# BEP33_2panel_v2b.net
KiCad netlist of a schematic drawn in EAGLE
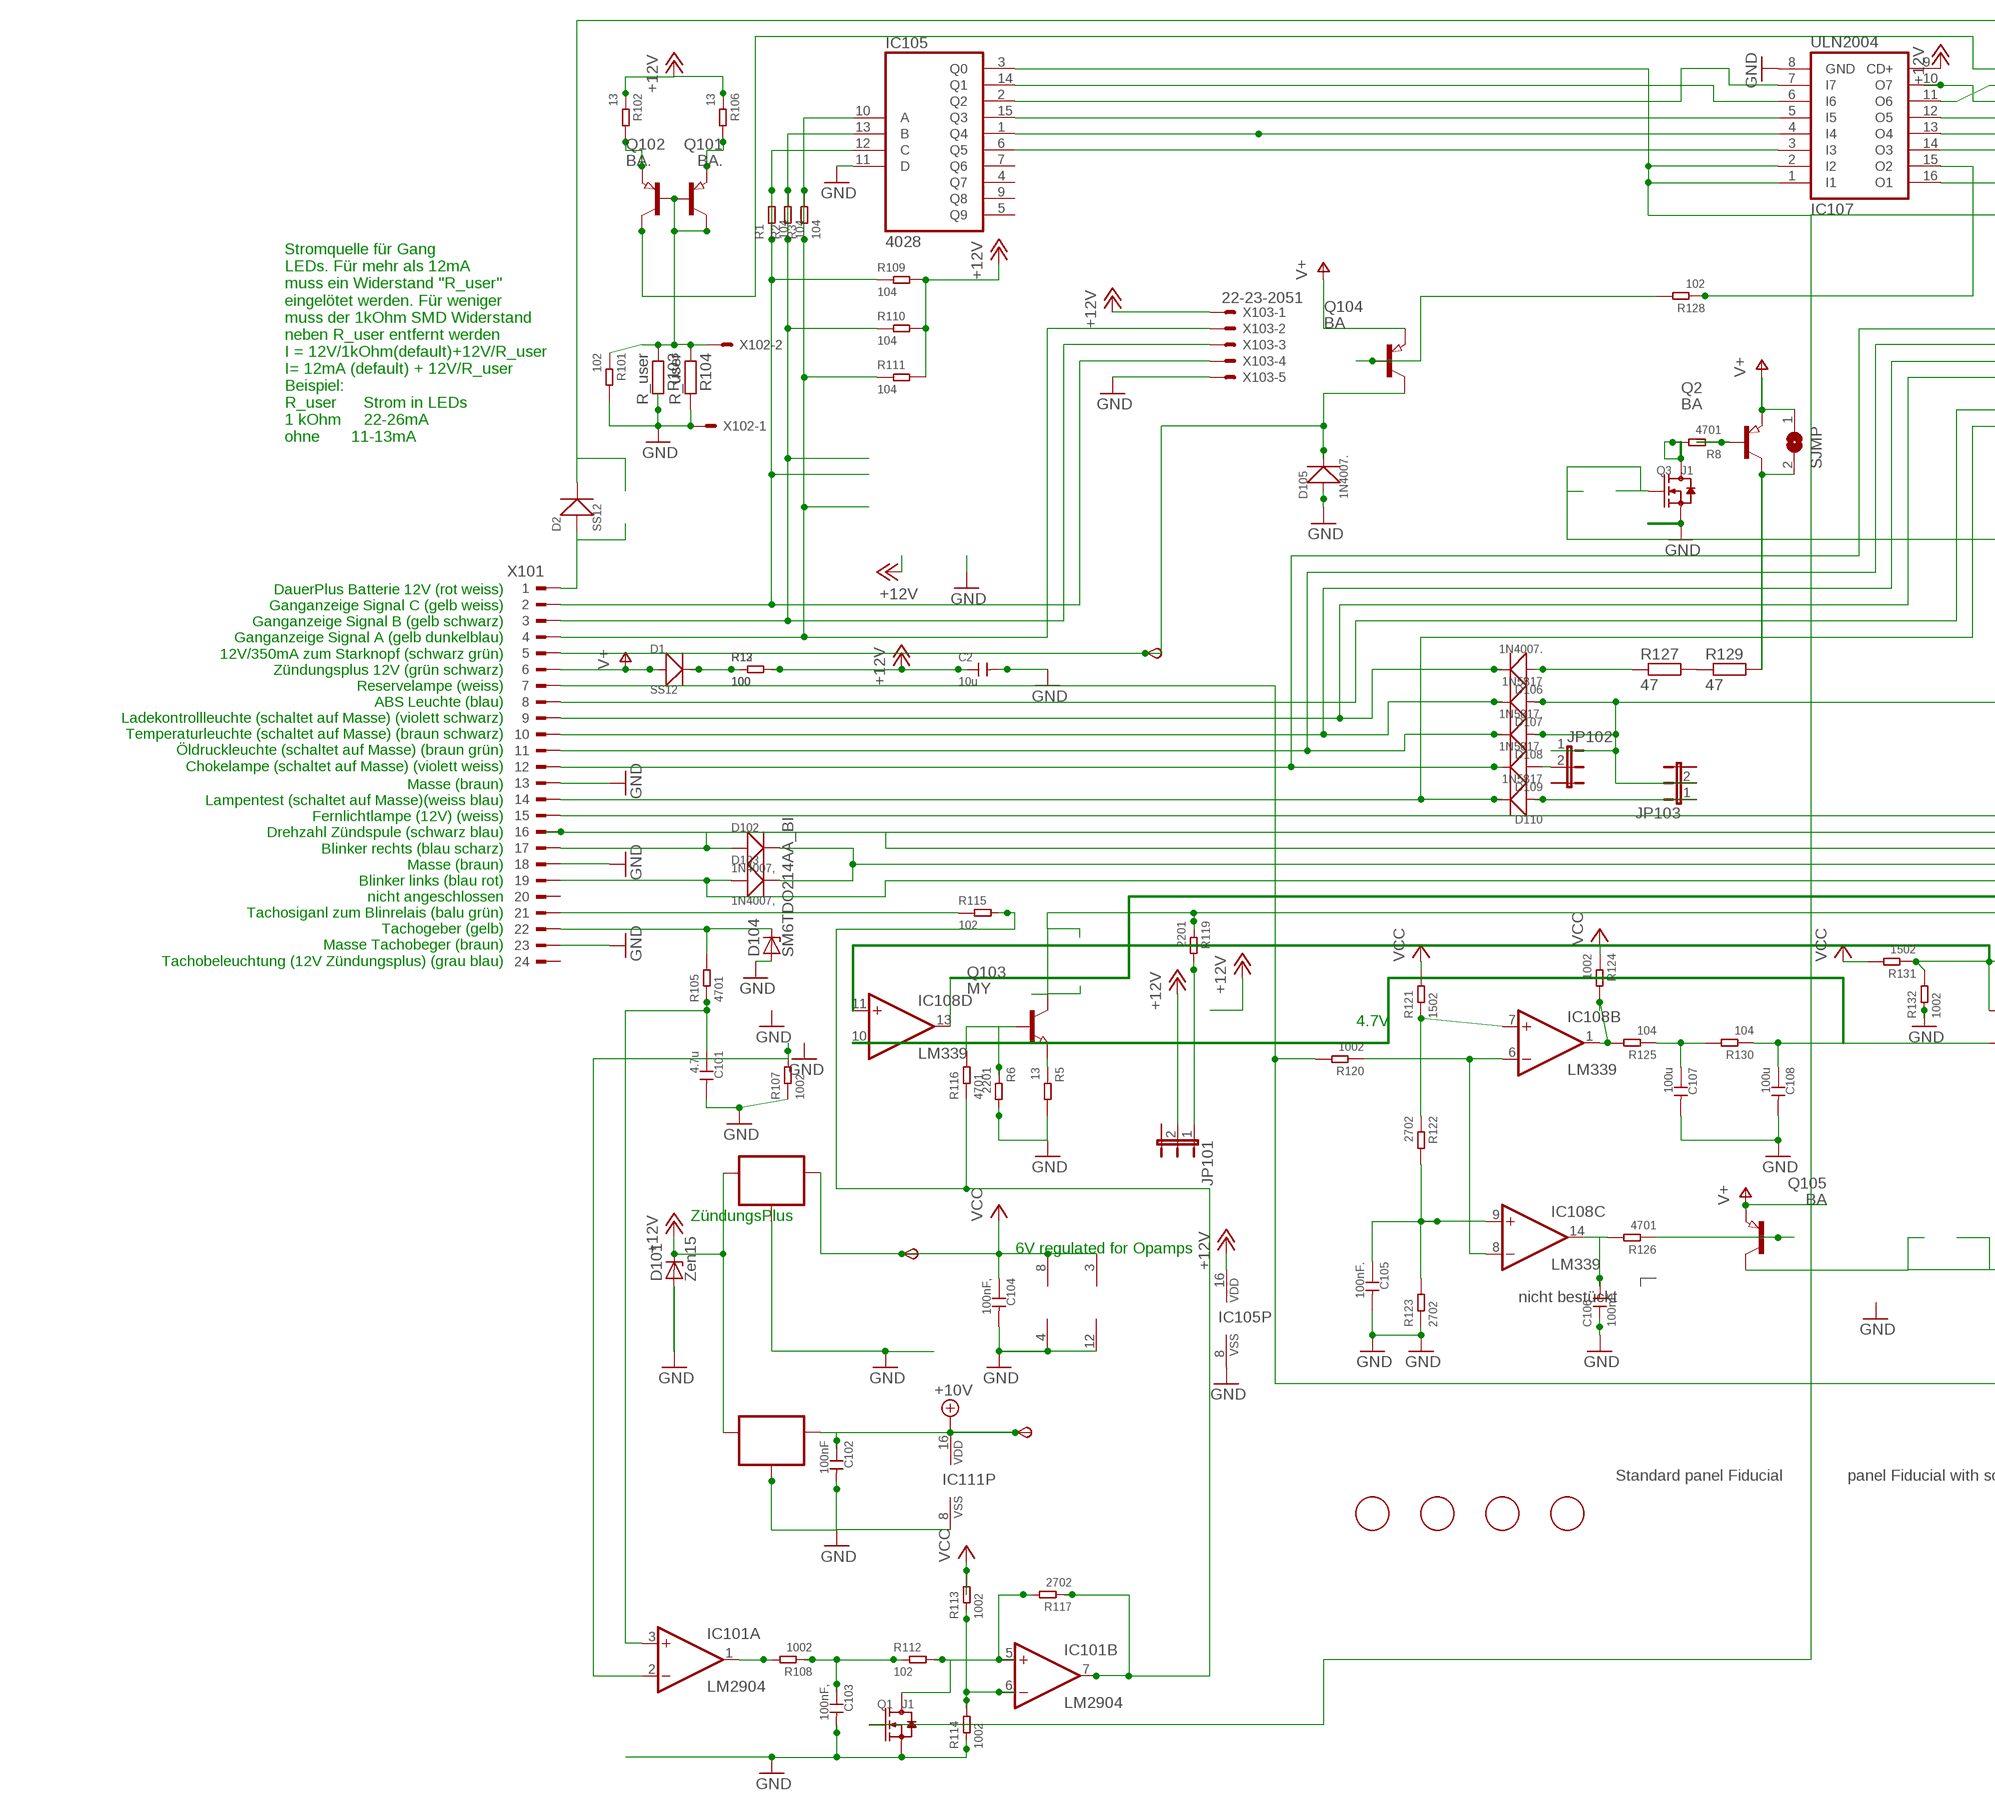
[diagram p0: schematic, sheet 1, part 1 of 2]
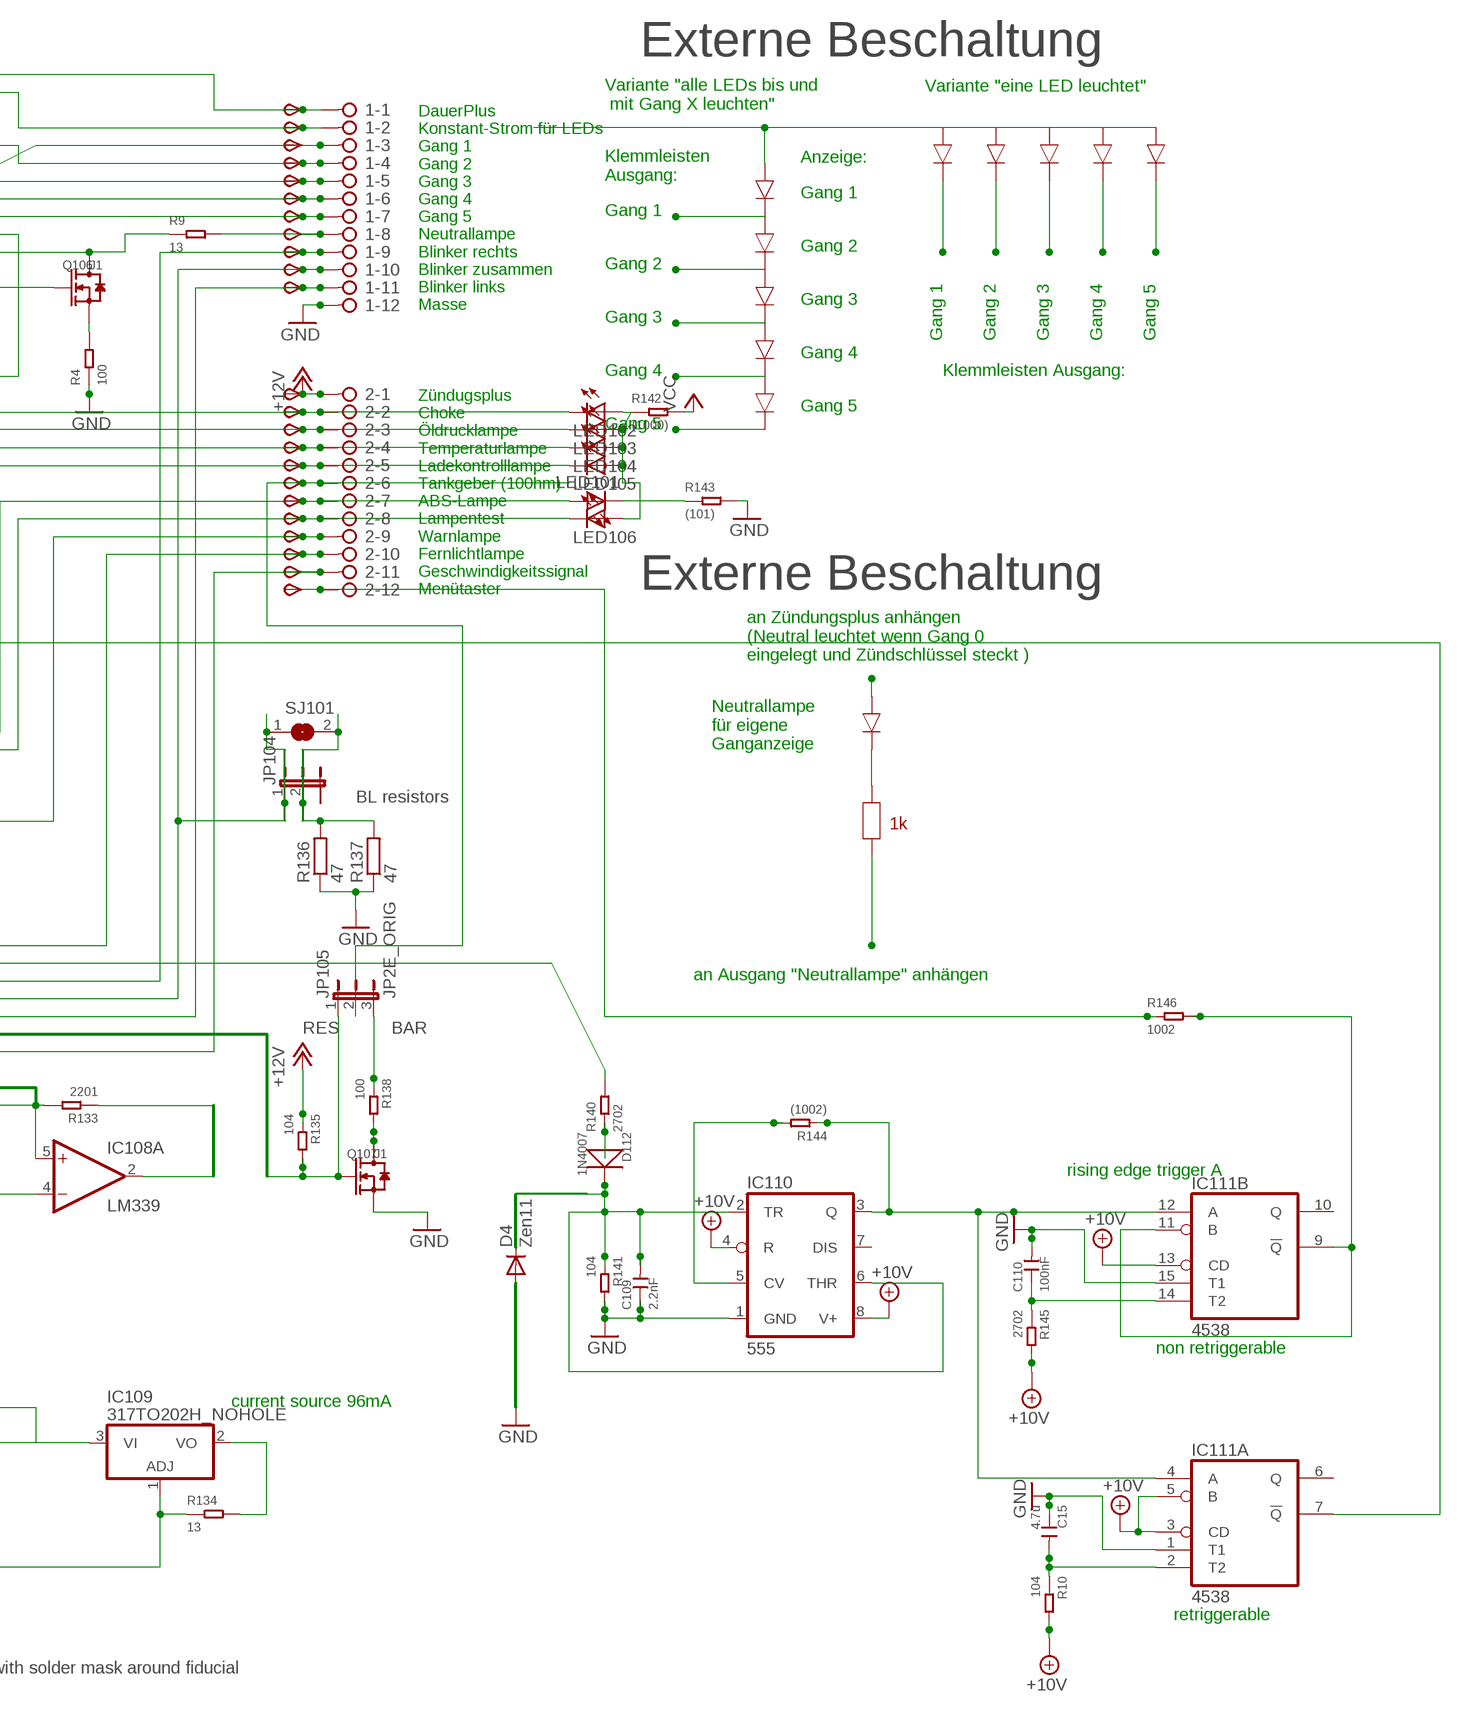
[diagram p1: schematic, sheet 1, part 2 of 2]

(export (version "E")
  (design (tool "Eeschema 10.0.6"))
  (components
    (comp (ref "1")
      (value "2081-1132")
      (footprint "eagle-import:12-PIN")
      (libsource (lib "eagle-import") (part "2081-1132"))
    )
    (comp (ref "2")
      (value "2081-1132")
      (footprint "eagle-import:12-PIN")
      (libsource (lib "eagle-import") (part "2081-1132"))
    )
    (comp (ref "6V")
      (value "TPSB2.0")
      (footprint "eagle-import:B2.0")
      (libsource (lib "eagle-import") (part "TPSB2.0"))
    )
    (comp (ref "10V")
      (value "TPSB2.0")
      (footprint "eagle-import:B2.0")
      (libsource (lib "eagle-import") (part "TPSB2.0"))
    )
    (comp (ref "C2")
      (value "10u")
      (footprint "eagle-import:C1206")
      (fields (field (name "MPN") "GRM31CR60J107ME39L"))
      (libsource (lib "eagle-import") (part "CERAMIC-100UF-6.3V-20%-X5R(1206)"))
    )
    (comp (ref "C15")
      (value "4.7u")
      (footprint "eagle-import:C0805")
      (fields (field (name "MPN") "CC0805KKX5R8BB475"))
      (libsource (lib "eagle-import") (part "CERAMIC-4.7UF-25V-10%-X5R(0805)"))
    )
    (comp (ref "C101")
      (value "4.7u")
      (footprint "eagle-import:C0805")
      (fields (field (name "MPN") "CC0805KKX5R8BB475"))
      (libsource (lib "eagle-import") (part "CERAMIC-4.7UF-25V-10%-X5R(0805)"))
    )
    (comp (ref "C102")
      (value "100nF")
      (footprint "eagle-import:C0805")
      (fields (field (name "MPN") "CC0805KRX7R9BB104"))
      (libsource (lib "eagle-import") (part "CERAMIC-100NF-50V-10%-X7R(0805)"))
    )
    (comp (ref "C103")
      (value "100nF,")
      (footprint "eagle-import:C0805")
      (fields (field (name "MPN") "CC0805KRX7R9BB104"))
      (libsource (lib "eagle-import") (part "CERAMIC-100NF-50V-10%-X7R(0805)"))
    )
    (comp (ref "C104")
      (value "100nF,")
      (footprint "eagle-import:C0805")
      (fields (field (name "MPN") "CC0805KRX7R9BB104"))
      (libsource (lib "eagle-import") (part "CERAMIC-100NF-50V-10%-X7R(0805)"))
    )
    (comp (ref "C105")
      (value "100nF.")
      (footprint "eagle-import:C0805")
      (fields (field (name "MPN") "CC0805KRX7R9BB104"))
      (libsource (lib "eagle-import") (part "CERAMIC-100NF-50V-10%-X7R(0805)"))
    )
    (comp (ref "C106")
      (value "100nF.")
      (footprint "eagle-import:C0805")
      (fields (field (name "MPN") "CC0805KRX7R9BB104"))
      (libsource (lib "eagle-import") (part "CERAMIC-100NF-50V-10%-X7R(0805)"))
    )
    (comp (ref "C107")
      (value "100u")
      (footprint "eagle-import:C1206")
      (fields (field (name "MPN") "GRM31CR60J107ME39L"))
      (libsource (lib "eagle-import") (part "CERAMIC-100UF-6.3V-20%-X5R(1206)"))
    )
    (comp (ref "C108")
      (value "100u")
      (footprint "eagle-import:C1206")
      (fields (field (name "MPN") "GRM31CR60J107ME39L"))
      (libsource (lib "eagle-import") (part "CERAMIC-100UF-6.3V-20%-X5R(1206)"))
    )
    (comp (ref "C109")
      (value "2.2nF")
      (footprint "eagle-import:C0805")
      (fields (field (name "MPN") "CC0805KRX7R9BB104"))
      (libsource (lib "eagle-import") (part "CERAMIC-100NF-50V-10%-X7R(0805)"))
    )
    (comp (ref "C110")
      (value "100nF")
      (footprint "eagle-import:C0805")
      (fields (field (name "MPN") "CC0805KRX7R9BB104"))
      (libsource (lib "eagle-import") (part "CERAMIC-100NF-50V-10%-X7R(0805)"))
    )
    (comp (ref "D1")
      (value "SS12")
      (footprint "eagle-import:DO-214AC_SLIM")
      (libsource (lib "eagle-import") (part "DIODE-GEN-PURPOSE-1KV-1A(DO-214AC)DO-214AC/1206"))
    )
    (comp (ref "D2")
      (value "SS12")
      (footprint "eagle-import:DO-214AC_SLIM")
      (libsource (lib "eagle-import") (part "DIODE-GEN-PURPOSE-1KV-1A(DO-214AC)DO-214AC/1206"))
    )
    (comp (ref "D4")
      (value "Zen11")
      (footprint "eagle-import:SOD-123_MINI-SMA")
      (libsource (lib "eagle-import") (part "CGRM400-G1"))
    )
    (comp (ref "D101")
      (value "Zen15")
      (footprint "eagle-import:DO214AA")
      (libsource (lib "eagle-import") (part "SM6T"))
    )
    (comp (ref "D102")
      (value "1N4007,")
      (footprint "eagle-import:DO-214AC")
      (fields (field (name "MPN") "1N4007"))
      (libsource (lib "eagle-import") (part "DIODE-GEN-PURPOSE-1KV-1A(DO-214AC)"))
    )
    (comp (ref "D103")
      (value "1N4007,")
      (footprint "eagle-import:DO-214AC")
      (fields (field (name "MPN") "1N4007"))
      (libsource (lib "eagle-import") (part "DIODE-GEN-PURPOSE-1KV-1A(DO-214AC)"))
    )
    (comp (ref "D104")
      (value "SM6TDO214AA_BI")
      (footprint "eagle-import:DO214AA_BI")
      (libsource (lib "eagle-import") (part "SM6TDO214AA_BI"))
    )
    (comp (ref "D105")
      (value "1N4007.")
      (footprint "eagle-import:DO-214AC")
      (fields (field (name "MPN") "1N4007"))
      (libsource (lib "eagle-import") (part "DIODE-GEN-PURPOSE-1KV-1A(DO-214AC)"))
    )
    (comp (ref "D106")
      (value "1N4007.")
      (footprint "eagle-import:DO-214AC")
      (fields (field (name "MPN") "1N4007"))
      (libsource (lib "eagle-import") (part "DIODE-GEN-PURPOSE-1KV-1A(DO-214AC)"))
    )
    (comp (ref "D107")
      (value "1N5817")
      (footprint "eagle-import:DO-214AC_SLIM")
      (libsource (lib "eagle-import") (part "DIODE-GEN-PURPOSE-1KV-1A(DO-214AC)DO-214AC/1206"))
    )
    (comp (ref "D108")
      (value "1N5817.")
      (footprint "eagle-import:DO-214AC_SLIM")
      (libsource (lib "eagle-import") (part "DIODE-GEN-PURPOSE-1KV-1A(DO-214AC)DO-214AC/1206"))
    )
    (comp (ref "D109")
      (value "1N5817.")
      (footprint "eagle-import:DO-214AC_SLIM")
      (libsource (lib "eagle-import") (part "DIODE-GEN-PURPOSE-1KV-1A(DO-214AC)DO-214AC/1206"))
    )
    (comp (ref "D110")
      (value "1N5817")
      (footprint "eagle-import:DO-214AC_SLIM")
      (libsource (lib "eagle-import") (part "DIODE-GEN-PURPOSE-1KV-1A(DO-214AC)DO-214AC/1206"))
    )
    (comp (ref "D112")
      (value "1N4007")
      (footprint "eagle-import:DO-214AC")
      (libsource (lib "eagle-import") (part "DIODE-GEN-PURPOSE-1KV-1A(DO-214AC)"))
    )
    (comp (ref "FID101")
      (value "FIDUCIAL")
      (footprint "eagle-import:FIDUCIAL_1MM")
      (libsource (lib "eagle-import") (part "FIDUCIAL"))
    )
    (comp (ref "FID102")
      (value "FIDUCIAL")
      (footprint "eagle-import:FIDUCIAL_1MM")
      (libsource (lib "eagle-import") (part "FIDUCIAL"))
    )
    (comp (ref "FID103")
      (value "FIDUCIAL")
      (footprint "eagle-import:FIDUCIAL_1MM")
      (libsource (lib "eagle-import") (part "FIDUCIAL"))
    )
    (comp (ref "FID104")
      (value "FIDUCIAL")
      (footprint "eagle-import:FIDUCIAL_1MM")
      (libsource (lib "eagle-import") (part "FIDUCIAL"))
    )
    (comp (ref "IC101")
      (value "LM2904")
      (footprint "eagle-import:SO08")
      (libsource (lib "eagle-import") (part "LM358D"))
    )
    (comp (ref "IC102")
      (value "78L06")
      (footprint "eagle-import:SOT89_ROUND")
      (libsource (lib "eagle-import") (part "78LXXSOT89_ROUND"))
    )
    (comp (ref "IC104")
      (value "78L10")
      (footprint "eagle-import:SOT89_ROUND")
      (libsource (lib "eagle-import") (part "78LXXSOT89_ROUND"))
    )
    (comp (ref "IC105")
      (value "4028")
      (footprint "eagle-import:SO16")
      (libsource (lib "eagle-import") (part "4028D"))
    )
    (comp (ref "IC107")
      (value "ULN2004")
      (footprint "eagle-import:SO16")
      (libsource (lib "eagle-import") (part "ULN2004AD"))
    )
    (comp (ref "IC108")
      (value "LM339")
      (footprint "eagle-import:SO14")
      (libsource (lib "eagle-import") (part "LM339D"))
    )
    (comp (ref "IC109")
      (value "317TO202H_NOHOLE")
      (footprint "eagle-import:TO220H_NOHOLE")
      (libsource (lib "eagle-import") (part "317TO202H_NOHOLE"))
    )
    (comp (ref "IC110")
      (value "555")
      (footprint "eagle-import:SO08")
      (libsource (lib "eagle-import") (part "555DNE"))
    )
    (comp (ref "IC111")
      (value "4538")
      (footprint "eagle-import:SO16")
      (libsource (lib "eagle-import") (part "4538D"))
    )
    (comp (ref "JP101")
      (value "JP2EJP2_SMALLPADS")
      (footprint "eagle-import:JP2_SMALLPADS")
      (libsource (lib "eagle-import") (part "JP2EJP2_SMALLPADS"))
    )
    (comp (ref "JP102")
      (value "JP2EJP2_SMALLPADS")
      (footprint "eagle-import:JP2_SMALLPADS")
      (libsource (lib "eagle-import") (part "JP2EJP2_SMALLPADS"))
    )
    (comp (ref "JP103")
      (value "JP2EJP2_SMALLPADS")
      (footprint "eagle-import:JP2_SMALLPADS")
      (libsource (lib "eagle-import") (part "JP2EJP2_SMALLPADS"))
    )
    (comp (ref "JP104")
      (value "JP2EJP2_SMALLPADS")
      (footprint "eagle-import:JP2_SMALLPADS")
      (libsource (lib "eagle-import") (part "JP2EJP2_SMALLPADS"))
    )
    (comp (ref "JP105")
      (value "JP2E_ORIG")
      (footprint "eagle-import:JP2_ORIG_SMALLPADS")
      (libsource (lib "eagle-import") (part "JP2E_ORIG"))
    )
    (comp (ref "LED101")
      (value "LEDLD260")
      (footprint "eagle-import:LD260")
      (libsource (lib "eagle-import") (part "LEDLD260"))
    )
    (comp (ref "LED102")
      (value "LEDLD260")
      (footprint "eagle-import:LD260")
      (libsource (lib "eagle-import") (part "LEDLD260"))
    )
    (comp (ref "LED103")
      (value "LEDLD260")
      (footprint "eagle-import:LD260")
      (libsource (lib "eagle-import") (part "LEDLD260"))
    )
    (comp (ref "LED104")
      (value "LEDLD260")
      (footprint "eagle-import:LD260")
      (libsource (lib "eagle-import") (part "LEDLD260"))
    )
    (comp (ref "LED105")
      (value "LEDLD260")
      (footprint "eagle-import:LD260")
      (libsource (lib "eagle-import") (part "LEDLD260"))
    )
    (comp (ref "LED106")
      (value "LEDLD260")
      (footprint "eagle-import:LD260")
      (libsource (lib "eagle-import") (part "LEDLD260"))
    )
    (comp (ref "Q1")
      (value "J1")
      (footprint "eagle-import:SOT-23")
      (fields (field (name "MPN") "BSS138W-7-F"))
      (libsource (lib "eagle-import") (part "SMD-MOSFET-N-CH-50V-200MA-BSS138W-7-F(SOT-23)"))
    )
    (comp (ref "Q2")
      (value "BA")
      (footprint "eagle-import:SOT89")
      (libsource (lib "eagle-import") (part "PNP-TRANSISTOR_SOT89"))
    )
    (comp (ref "Q3")
      (value "J1")
      (footprint "eagle-import:SOT-23")
      (fields (field (name "MPN") "BSS138W-7-F"))
      (libsource (lib "eagle-import") (part "SMD-MOSFET-N-CH-50V-200MA-BSS138W-7-F(SOT-23)"))
    )
    (comp (ref "Q101")
      (value "BA.")
      (footprint "eagle-import:SOT89")
      (libsource (lib "eagle-import") (part "PNP-TRANSISTOR_SOT89"))
    )
    (comp (ref "Q102")
      (value "BA.")
      (footprint "eagle-import:SOT89")
      (libsource (lib "eagle-import") (part "PNP-TRANSISTOR_SOT89"))
    )
    (comp (ref "Q103")
      (value "MY")
      (footprint "eagle-import:SOT89")
      (libsource (lib "eagle-import") (part "NPN-TRANSISTOR_SOT89"))
    )
    (comp (ref "Q104")
      (value "BA")
      (footprint "eagle-import:SOT89")
      (libsource (lib "eagle-import") (part "PNP-TRANSISTOR_SOT89"))
    )
    (comp (ref "Q105")
      (value "BA")
      (footprint "eagle-import:SOT89")
      (libsource (lib "eagle-import") (part "PNP-TRANSISTOR_SOT89"))
    )
    (comp (ref "Q106")
      (value "J1")
      (footprint "eagle-import:SOT-23")
      (fields (field (name "MPN") "BSS138W-7-F"))
      (libsource (lib "eagle-import") (part "SMD-MOSFET-N-CH-50V-200MA-BSS138W-7-F(SOT-23)"))
    )
    (comp (ref "Q107")
      (value "J1")
      (footprint "eagle-import:SOT-23")
      (fields (field (name "MPN") "BSS138W-7-F"))
      (libsource (lib "eagle-import") (part "SMD-MOSFET-N-CH-50V-200MA-BSS138W-7-F(SOT-23)"))
    )
    (comp (ref "R1")
      (value "104")
      (footprint "eagle-import:R0805")
      (fields (field (name "MPN") "RC0805FR-0710KL"))
      (libsource (lib "eagle-import") (part "SMD-RES-10K-1%-1/8W(0805)"))
    )
    (comp (ref "R2")
      (value "104")
      (footprint "eagle-import:R0805")
      (fields (field (name "MPN") "RC0805FR-0710KL"))
      (libsource (lib "eagle-import") (part "SMD-RES-10K-1%-1/8W(0805)"))
    )
    (comp (ref "R3")
      (value "104")
      (footprint "eagle-import:R0805")
      (fields (field (name "MPN") "RC0805FR-0710KL"))
      (libsource (lib "eagle-import") (part "SMD-RES-10K-1%-1/8W(0805)"))
    )
    (comp (ref "R4")
      (value "100")
      (footprint "eagle-import:R0805")
      (fields (field (name "MPN") "RC0805JR-07220RL"))
      (libsource (lib "eagle-import") (part "SMD-RES-220R-5%-1/8W(0805)"))
    )
    (comp (ref "R5")
      (value "13")
      (footprint "eagle-import:R1206")
      (fields (field (name "MPN") "RC1206JR-0713RL"))
      (libsource (lib "eagle-import") (part "SMD-RES-13R-5%-1/4W(1206)"))
    )
    (comp (ref "R6")
      (value "2201")
      (footprint "eagle-import:R0805")
      (fields (field (name "MPN") "RC0805JR-071KL"))
      (libsource (lib "eagle-import") (part "SMD-RES-1K-5%-1/8W(0805)"))
    )
    (comp (ref "R8")
      (value "4701")
      (footprint "eagle-import:R0805")
      (fields (field (name "MPN") "RC0805JR-074K7L"))
      (libsource (lib "eagle-import") (part "SMD-RES-4.7K-5%-1/8W(0805)"))
    )
    (comp (ref "R9")
      (value "13")
      (footprint "eagle-import:R1206")
      (fields (field (name "MPN") "RC1206JR-0713RL"))
      (libsource (lib "eagle-import") (part "SMD-RES-13R-5%-1/4W(1206)"))
    )
    (comp (ref "R10")
      (value "104")
      (footprint "eagle-import:R0805")
      (fields (field (name "MPN") "RC0805JR-074K7L"))
      (libsource (lib "eagle-import") (part "SMD-RES-4.7K-5%-1/8W(0805)"))
    )
    (comp (ref "R12")
      (value "100")
      (footprint "eagle-import:R0805")
      (fields (field (name "MPN") "RC0805JR-072K2L"))
      (libsource (lib "eagle-import") (part "SMD-RES-2.2K-5%-1/8W(0805)"))
    )
    (comp (ref "R13")
      (value "100")
      (footprint "eagle-import:R0805")
      (fields (field (name "MPN") "RC0805JR-072K2L"))
      (libsource (lib "eagle-import") (part "SMD-RES-2.2K-5%-1/8W(0805)"))
    )
    (comp (ref "R101")
      (value "102")
      (footprint "eagle-import:R0805")
      (fields (field (name "MPN") "RC0805JR-071KL"))
      (libsource (lib "eagle-import") (part "SMD-RES-1K-5%-1/8W(0805)"))
    )
    (comp (ref "R102")
      (value "13")
      (footprint "eagle-import:R1206")
      (fields (field (name "MPN") "RC1206JR-0713RL"))
      (libsource (lib "eagle-import") (part "SMD-RES-13R-5%-1/4W(1206)"))
    )
    (comp (ref "R103")
      (value "R_user")
      (footprint "eagle-import:R0805")
      (libsource (lib "eagle-import") (part "R-EU_R0805"))
    )
    (comp (ref "R104")
      (value "R_user")
      (footprint "eagle-import:R0805")
      (libsource (lib "eagle-import") (part "R-EU_R0805"))
    )
    (comp (ref "R105")
      (value "4701")
      (footprint "eagle-import:R0805")
      (fields (field (name "MPN") "RC0805JR-074K7L"))
      (libsource (lib "eagle-import") (part "SMD-RES-4.7K-5%-1/8W(0805)"))
    )
    (comp (ref "R106")
      (value "13")
      (footprint "eagle-import:R1206")
      (fields (field (name "MPN") "RC1206JR-0713RL"))
      (libsource (lib "eagle-import") (part "SMD-RES-13R-5%-1/4W(1206)"))
    )
    (comp (ref "R107")
      (value "1002")
      (footprint "eagle-import:R0805")
      (fields (field (name "MPN") "RC0805FR-0710KL"))
      (libsource (lib "eagle-import") (part "SMD-RES-10K-1%-1/8W(0805)"))
    )
    (comp (ref "R108")
      (value "1002")
      (footprint "eagle-import:R0805")
      (fields (field (name "MPN") "RC0805FR-0710KL"))
      (libsource (lib "eagle-import") (part "SMD-RES-10K-1%-1/8W(0805)"))
    )
    (comp (ref "R109")
      (value "104")
      (footprint "eagle-import:R0805")
      (fields (field (name "MPN") "RC0805FR-0710KL"))
      (libsource (lib "eagle-import") (part "SMD-RES-10K-1%-1/8W(0805)"))
    )
    (comp (ref "R110")
      (value "104")
      (footprint "eagle-import:R0805")
      (fields (field (name "MPN") "RC0805FR-0710KL"))
      (libsource (lib "eagle-import") (part "SMD-RES-10K-1%-1/8W(0805)"))
    )
    (comp (ref "R111")
      (value "104")
      (footprint "eagle-import:R0805")
      (fields (field (name "MPN") "RC0805FR-0710KL"))
      (libsource (lib "eagle-import") (part "SMD-RES-10K-1%-1/8W(0805)"))
    )
    (comp (ref "R112")
      (value "102")
      (footprint "eagle-import:R0805")
      (fields (field (name "MPN") "RC0805JR-071KL"))
      (libsource (lib "eagle-import") (part "SMD-RES-1K-5%-1/8W(0805)"))
    )
    (comp (ref "R113")
      (value "1002")
      (footprint "eagle-import:R0805")
      (fields (field (name "MPN") "RC0805JR-071KL"))
      (libsource (lib "eagle-import") (part "SMD-RES-1K-5%-1/8W(0805)"))
    )
    (comp (ref "R114")
      (value "1002")
      (footprint "eagle-import:R0805")
      (fields (field (name "MPN") "RC0805JR-071KL"))
      (libsource (lib "eagle-import") (part "SMD-RES-1K-5%-1/8W(0805)"))
    )
    (comp (ref "R115")
      (value "102")
      (footprint "eagle-import:R0805")
      (fields (field (name "MPN") "RC0805JR-07220RL"))
      (libsource (lib "eagle-import") (part "SMD-RES-220R-5%-1/8W(0805)"))
    )
    (comp (ref "R116")
      (value "4701")
      (footprint "eagle-import:R0805")
      (fields (field (name "MPN") "RC0805JR-074K7L"))
      (libsource (lib "eagle-import") (part "SMD-RES-4.7K-5%-1/8W(0805)"))
    )
    (comp (ref "R117")
      (value "2702")
      (footprint "eagle-import:R0805")
      (fields (field (name "MPN") "RC0805JR-074K7L"))
      (libsource (lib "eagle-import") (part "SMD-RES-4.7K-5%-1/8W(0805)"))
    )
    (comp (ref "R119")
      (value "2201")
      (footprint "eagle-import:R0805")
      (fields (field (name "MPN") "RC0805JR-072K2L"))
      (libsource (lib "eagle-import") (part "SMD-RES-2.2K-5%-1/8W(0805)"))
    )
    (comp (ref "R120")
      (value "1002")
      (footprint "eagle-import:R0805")
      (fields (field (name "MPN") "RC0805FR-0710KL"))
      (libsource (lib "eagle-import") (part "SMD-RES-10K-1%-1/8W(0805)"))
    )
    (comp (ref "R121")
      (value "1502")
      (footprint "eagle-import:R0805")
      (fields (field (name "MPN") "RC0805FR-0710KL"))
      (libsource (lib "eagle-import") (part "SMD-RES-10K-1%-1/8W(0805)"))
    )
    (comp (ref "R122")
      (value "2702")
      (footprint "eagle-import:R0805")
      (fields (field (name "MPN") "RC0805JR-074K7L"))
      (libsource (lib "eagle-import") (part "SMD-RES-4.7K-5%-1/8W(0805)"))
    )
    (comp (ref "R123")
      (value "2702")
      (footprint "eagle-import:R0805")
      (fields (field (name "MPN") "RC0805JR-074K7L"))
      (libsource (lib "eagle-import") (part "SMD-RES-4.7K-5%-1/8W(0805)"))
    )
    (comp (ref "R124")
      (value "1002")
      (footprint "eagle-import:R0805")
      (fields (field (name "MPN") "RC0805FR-0710KL"))
      (libsource (lib "eagle-import") (part "SMD-RES-10K-1%-1/8W(0805)"))
    )
    (comp (ref "R125")
      (value "104")
      (footprint "eagle-import:R0805")
      (fields (field (name "MPN") "RC0805FR-0710KL"))
      (libsource (lib "eagle-import") (part "SMD-RES-10K-1%-1/8W(0805)"))
    )
    (comp (ref "R126")
      (value "4701")
      (footprint "eagle-import:R0805")
      (fields (field (name "MPN") "RC0805JR-074K7L"))
      (libsource (lib "eagle-import") (part "SMD-RES-4.7K-5%-1/8W(0805)"))
    )
    (comp (ref "R127")
      (value "47")
      (footprint "eagle-import:V235_17_1MM")
      (libsource (lib "eagle-import") (part "R-EU_V235/17_1MM"))
    )
    (comp (ref "R128")
      (value "102")
      (footprint "eagle-import:R0805")
      (fields (field (name "MPN") "RC0805JR-071KL"))
      (libsource (lib "eagle-import") (part "SMD-RES-1K-5%-1/8W(0805)"))
    )
    (comp (ref "R129")
      (value "47")
      (footprint "eagle-import:V235_17_1MM")
      (libsource (lib "eagle-import") (part "R-EU_V235/17_1MM"))
    )
    (comp (ref "R130")
      (value "104")
      (footprint "eagle-import:R0805")
      (fields (field (name "MPN") "RC0805FR-0710KL"))
      (libsource (lib "eagle-import") (part "SMD-RES-10K-1%-1/8W(0805)"))
    )
    (comp (ref "R131")
      (value "1502")
      (footprint "eagle-import:R0805")
      (fields (field (name "MPN") "RC0805FR-0710KL"))
      (libsource (lib "eagle-import") (part "SMD-RES-10K-1%-1/8W(0805)"))
    )
    (comp (ref "R132")
      (value "1002")
      (footprint "eagle-import:R0805")
      (fields (field (name "MPN") "RC0805FR-0710KL"))
      (libsource (lib "eagle-import") (part "SMD-RES-10K-1%-1/8W(0805)"))
    )
    (comp (ref "R133")
      (value "2201")
      (footprint "eagle-import:R0805")
      (fields (field (name "MPN") "RC0805JR-072K2L"))
      (libsource (lib "eagle-import") (part "SMD-RES-2.2K-5%-1/8W(0805)"))
    )
    (comp (ref "R134")
      (value "13")
      (footprint "eagle-import:R1206")
      (fields (field (name "MPN") "RC1206JR-0713RL"))
      (libsource (lib "eagle-import") (part "SMD-RES-13R-5%-1/4W(1206)"))
    )
    (comp (ref "R135")
      (value "104")
      (footprint "eagle-import:R0805")
      (fields (field (name "MPN") "RC0805FR-0710KL"))
      (libsource (lib "eagle-import") (part "SMD-RES-10K-1%-1/8W(0805)"))
    )
    (comp (ref "R136")
      (value "47")
      (footprint "eagle-import:V235_17_1MM")
      (libsource (lib "eagle-import") (part "R-EU_V235/17_1MM"))
    )
    (comp (ref "R137")
      (value "47")
      (footprint "eagle-import:V235_17_1MM")
      (libsource (lib "eagle-import") (part "R-EU_V235/17_1MM"))
    )
    (comp (ref "R138")
      (value "100")
      (footprint "eagle-import:R0805")
      (fields (field (name "MPN") "RC0805JR-072K2L"))
      (libsource (lib "eagle-import") (part "SMD-RES-2.2K-5%-1/8W(0805)"))
    )
    (comp (ref "R140")
      (value "2702")
      (footprint "eagle-import:R0805")
      (fields (field (name "MPN") "RC0805FR-0710KL"))
      (libsource (lib "eagle-import") (part "SMD-RES-10K-1%-1/8W(0805)"))
    )
    (comp (ref "R141")
      (value "104")
      (footprint "eagle-import:R0805")
      (fields (field (name "MPN") "RC0805FR-0710KL"))
      (libsource (lib "eagle-import") (part "SMD-RES-10K-1%-1/8W(0805)"))
    )
    (comp (ref "R142")
      (value "(1000)")
      (footprint "eagle-import:R0805")
      (fields (field (name "MPN") "RC0805JR-07100RL"))
      (libsource (lib "eagle-import") (part "SMD-RES-100R-5%-1/8W(0805)"))
    )
    (comp (ref "R143")
      (value "(101)")
      (footprint "eagle-import:R0805")
      (fields (field (name "MPN") "RC0805JR-07100RL"))
      (libsource (lib "eagle-import") (part "SMD-RES-100R-5%-1/8W(0805)"))
    )
    (comp (ref "R144")
      (value "(1002)")
      (footprint "eagle-import:R0805")
      (fields (field (name "MPN") "RC0805FR-0710KL"))
      (libsource (lib "eagle-import") (part "SMD-RES-10K-1%-1/8W(0805)"))
    )
    (comp (ref "R145")
      (value "2702")
      (footprint "eagle-import:R0805")
      (fields (field (name "MPN") "RC0805JR-074K7L"))
      (libsource (lib "eagle-import") (part "SMD-RES-4.7K-5%-1/8W(0805)"))
    )
    (comp (ref "R146")
      (value "1002")
      (footprint "eagle-import:R0805")
      (fields (field (name "MPN") "RC0805JR-074K7L"))
      (libsource (lib "eagle-import") (part "SMD-RES-4.7K-5%-1/8W(0805)"))
    )
    (comp (ref "SJ101")
      (value "SJ")
      (footprint "eagle-import:SJ")
      (libsource (lib "eagle-import") (part "solder-jumper_SJ"))
    )
    (comp (ref "SJMP")
      (value "SJ")
      (footprint "eagle-import:SJ")
      (libsource (lib "eagle-import") (part "SJ"))
    )
    (comp (ref "START")
      (value "TPSB2.0")
      (footprint "eagle-import:B2.0")
      (libsource (lib "eagle-import") (part "TPSB2.0"))
    )
    (comp (ref "TP1")
      (value "TPSB2.0")
      (footprint "eagle-import:B2.0")
      (libsource (lib "eagle-import") (part "TPSB2.0"))
    )
    (comp (ref "TP2")
      (value "TPSB2.0")
      (footprint "eagle-import:B2.0")
      (libsource (lib "eagle-import") (part "TPSB2.0"))
    )
    (comp (ref "TP3")
      (value "TPSB2.0")
      (footprint "eagle-import:B2.0")
      (libsource (lib "eagle-import") (part "TPSB2.0"))
    )
    (comp (ref "TP4")
      (value "TPSB2.0")
      (footprint "eagle-import:B2.0")
      (libsource (lib "eagle-import") (part "TPSB2.0"))
    )
    (comp (ref "TP5")
      (value "TPSB2.0")
      (footprint "eagle-import:B2.0")
      (libsource (lib "eagle-import") (part "TPSB2.0"))
    )
    (comp (ref "TP6")
      (value "TPSB2.0")
      (footprint "eagle-import:B2.0")
      (libsource (lib "eagle-import") (part "TPSB2.0"))
    )
    (comp (ref "TP7")
      (value "TPSB2.0")
      (footprint "eagle-import:B2.0")
      (libsource (lib "eagle-import") (part "TPSB2.0"))
    )
    (comp (ref "TP8")
      (value "TPSB2.0")
      (footprint "eagle-import:B2.0")
      (libsource (lib "eagle-import") (part "TPSB2.0"))
    )
    (comp (ref "TP9")
      (value "TPSB2.0")
      (footprint "eagle-import:B2.0")
      (libsource (lib "eagle-import") (part "TPSB2.0"))
    )
    (comp (ref "TP10")
      (value "TPSB2.0")
      (footprint "eagle-import:B2.0")
      (libsource (lib "eagle-import") (part "TPSB2.0"))
    )
    (comp (ref "TP11")
      (value "TPSB2.0")
      (footprint "eagle-import:B2.0")
      (libsource (lib "eagle-import") (part "TPSB2.0"))
    )
    (comp (ref "TP12")
      (value "TPSB2.0")
      (footprint "eagle-import:B2.0")
      (libsource (lib "eagle-import") (part "TPSB2.0"))
    )
    (comp (ref "TP13")
      (value "TPSB2.0")
      (footprint "eagle-import:B2.0")
      (libsource (lib "eagle-import") (part "TPSB2.0"))
    )
    (comp (ref "TP16")
      (value "TPSB2.0")
      (footprint "eagle-import:B2.0")
      (libsource (lib "eagle-import") (part "TPSB2.0"))
    )
    (comp (ref "TP17")
      (value "TPSB2.0")
      (footprint "eagle-import:B2.0")
      (libsource (lib "eagle-import") (part "TPSB2.0"))
    )
    (comp (ref "TP18")
      (value "TPSB2.0")
      (footprint "eagle-import:B2.0")
      (libsource (lib "eagle-import") (part "TPSB2.0"))
    )
    (comp (ref "TP19")
      (value "TPSB2.0")
      (footprint "eagle-import:B2.0")
      (libsource (lib "eagle-import") (part "TPSB2.0"))
    )
    (comp (ref "TP21")
      (value "TPSB2.0")
      (footprint "eagle-import:B2.0")
      (libsource (lib "eagle-import") (part "TPSB2.0"))
    )
    (comp (ref "TP22")
      (value "TPSB2.0")
      (footprint "eagle-import:B2.0")
      (libsource (lib "eagle-import") (part "TPSB2.0"))
    )
    (comp (ref "TP23")
      (value "TPSB2.0")
      (footprint "eagle-import:B2.0")
      (libsource (lib "eagle-import") (part "TPSB2.0"))
    )
    (comp (ref "TP24")
      (value "TPSB1,27")
      (footprint "eagle-import:B1,27")
      (libsource (lib "eagle-import") (part "TPSB1,27"))
    )
    (comp (ref "TP25")
      (value "TPSB2.0")
      (footprint "eagle-import:B2.0")
      (libsource (lib "eagle-import") (part "TPSB2.0"))
    )
    (comp (ref "TP26")
      (value "TPSB2.0")
      (footprint "eagle-import:B2.0")
      (libsource (lib "eagle-import") (part "TPSB2.0"))
    )
    (comp (ref "X101")
      (value "CON_BMWV2")
      (footprint "eagle-import:24-PIN_V2")
      (libsource (lib "eagle-import") (part "CON_BMWV2"))
    )
    (comp (ref "X102")
      (value "22-23-2021")
      (footprint "eagle-import:22-23-2021")
      (fields (field (name "MF") "MOLEX"))
      (libsource (lib "eagle-import") (part "22-23-2021"))
    )
    (comp (ref "X103")
      (value "22-23-2051")
      (footprint "eagle-import:22-23-2051")
      (fields (field (name "MF") "MOLEX"))
      (libsource (lib "eagle-import") (part "22-23-2051"))
    )
  )
  (nets
    (net (code "1") (name "+10V") (class "Default")
      (node (ref "10V") (pin "TP") (pinfunction "PP_TP") (pintype "input"))
      (node (ref "C102") (pin "1") (pinfunction "1_1") (pintype "passive"))
      (node (ref "IC104") (pin "1") (pinfunction "OUT_1") (pintype "passive"))
      (node (ref "IC110") (pin "4") (pinfunction "R_4") (pintype "input"))
      (node (ref "IC110") (pin "8") (pinfunction "V+_8") (pintype "power_in"))
      (node (ref "IC111") (pin "13") (pinfunction "CD_13") (pintype "input"))
      (node (ref "IC111") (pin "16") (pinfunction "VDD_16") (pintype "power_in"))
      (node (ref "IC111") (pin "3") (pinfunction "CD_3") (pintype "input"))
      (node (ref "IC111") (pin "5") (pinfunction "B_5") (pintype "input"))
      (node (ref "R10") (pin "2") (pinfunction "2_2") (pintype "passive"))
      (node (ref "R145") (pin "2") (pinfunction "2_2") (pintype "passive"))
    )
    (net (code "2") (name "+12V") (class "Default")
      (node (ref "2") (pin "1") (pinfunction "KL_1") (pintype "passive"))
      (node (ref "C2") (pin "1") (pinfunction "1_1") (pintype "passive"))
      (node (ref "D101") (pin "C") (pinfunction "C_C") (pintype "passive"))
      (node (ref "IC102") (pin "3") (pinfunction "IN_3") (pintype "input"))
      (node (ref "IC104") (pin "3") (pinfunction "IN_3") (pintype "input"))
      (node (ref "IC105") (pin "16") (pinfunction "VDD_16") (pintype "power_in"))
      (node (ref "IC107") (pin "9") (pinfunction "CD+_9") (pintype "passive"))
      (node (ref "JP101") (pin "2") (pinfunction "2_2") (pintype "passive"))
      (node (ref "R102") (pin "1") (pinfunction "1_1") (pintype "passive"))
      (node (ref "R106") (pin "1") (pinfunction "1_1") (pintype "passive"))
      (node (ref "R109") (pin "2") (pinfunction "2_2") (pintype "passive"))
      (node (ref "R110") (pin "2") (pinfunction "2_2") (pintype "passive"))
      (node (ref "R111") (pin "2") (pinfunction "2_2") (pintype "passive"))
      (node (ref "R12") (pin "2") (pinfunction "2_2") (pintype "passive"))
      (node (ref "R13") (pin "2") (pinfunction "2_2") (pintype "passive"))
      (node (ref "R135") (pin "1") (pinfunction "1_1") (pintype "passive"))
      (node (ref "TP12") (pin "TP") (pinfunction "PP_TP") (pintype "input"))
      (node (ref "X103") (pin "1") (pinfunction "S_1") (pintype "passive"))
    )
    (net (code "3") (name "GND") (class "Default")
      (node (ref "1") (pin "12") (pinfunction "KL_12") (pintype "passive"))
      (node (ref "C101") (pin "2") (pinfunction "2_2") (pintype "passive"))
      (node (ref "C102") (pin "2") (pinfunction "2_2") (pintype "passive"))
      (node (ref "C103") (pin "2") (pinfunction "2_2") (pintype "passive"))
      (node (ref "C104") (pin "2") (pinfunction "2_2") (pintype "passive"))
      (node (ref "C105") (pin "2") (pinfunction "2_2") (pintype "passive"))
      (node (ref "C106") (pin "1") (pinfunction "1_1") (pintype "passive"))
      (node (ref "C107") (pin "2") (pinfunction "2_2") (pintype "passive"))
      (node (ref "C108") (pin "2") (pinfunction "2_2") (pintype "passive"))
      (node (ref "C109") (pin "1") (pinfunction "1_1") (pintype "passive"))
      (node (ref "C110") (pin "2") (pinfunction "2_2") (pintype "passive"))
      (node (ref "C15") (pin "1") (pinfunction "1_1") (pintype "passive"))
      (node (ref "C2") (pin "2") (pinfunction "2_2") (pintype "passive"))
      (node (ref "D101") (pin "A") (pinfunction "A_A") (pintype "passive"))
      (node (ref "D104") (pin "A") (pinfunction "A_A") (pintype "passive"))
      (node (ref "D105") (pin "1") (pinfunction "+_1") (pintype "passive"))
      (node (ref "D4") (pin "A") (pinfunction "A_A") (pintype "passive"))
      (node (ref "IC101") (pin "4") (pinfunction "V-_4") (pintype "power_in"))
      (node (ref "IC102") (pin "2") (pinfunction "GND_2") (pintype "input"))
      (node (ref "IC102") (pin "2@1") (pinfunction "GND_2@1") (pintype "input"))
      (node (ref "IC104") (pin "2") (pinfunction "GND_2") (pintype "input"))
      (node (ref "IC104") (pin "2@1") (pinfunction "GND_2@1") (pintype "input"))
      (node (ref "IC105") (pin "11") (pinfunction "D_11") (pintype "input"))
      (node (ref "IC105") (pin "8") (pinfunction "VSS_8") (pintype "power_in"))
      (node (ref "IC107") (pin "8") (pinfunction "GND_8") (pintype "power_in"))
      (node (ref "IC108") (pin "12") (pinfunction "GND_12") (pintype "power_in"))
      (node (ref "IC110") (pin "1") (pinfunction "GND_1") (pintype "power_in"))
      (node (ref "IC111") (pin "1") (pinfunction "T1_1") (pintype "input"))
      (node (ref "IC111") (pin "15") (pinfunction "T1_15") (pintype "input"))
      (node (ref "IC111") (pin "8") (pinfunction "VSS_8") (pintype "power_in"))
      (node (ref "Q1") (pin "2") (pinfunction "S_2") (pintype "passive"))
      (node (ref "Q107") (pin "2") (pinfunction "S_2") (pintype "passive"))
      (node (ref "Q3") (pin "2") (pinfunction "S_2") (pintype "passive"))
      (node (ref "R101") (pin "2") (pinfunction "2_2") (pintype "passive"))
      (node (ref "R103") (pin "2") (pinfunction "2_2") (pintype "passive"))
      (node (ref "R104") (pin "2") (pinfunction "2_2") (pintype "passive"))
      (node (ref "R107") (pin "1") (pinfunction "1_1") (pintype "passive"))
      (node (ref "R114") (pin "1") (pinfunction "1_1") (pintype "passive"))
      (node (ref "R123") (pin "1") (pinfunction "1_1") (pintype "passive"))
      (node (ref "R132") (pin "1") (pinfunction "1_1") (pintype "passive"))
      (node (ref "R136") (pin "1") (pinfunction "1_1") (pintype "passive"))
      (node (ref "R137") (pin "1") (pinfunction "1_1") (pintype "passive"))
      (node (ref "R141") (pin "2") (pinfunction "2_2") (pintype "passive"))
      (node (ref "R143") (pin "2") (pinfunction "2_2") (pintype "passive"))
      (node (ref "R4") (pin "1") (pinfunction "1_1") (pintype "passive"))
      (node (ref "R5") (pin "2") (pinfunction "2_2") (pintype "passive"))
      (node (ref "R6") (pin "2") (pinfunction "2_2") (pintype "passive"))
      (node (ref "X101") (pin "13") (pinfunction "13_13") (pintype "passive"))
      (node (ref "X101") (pin "18") (pinfunction "18_18") (pintype "passive"))
      (node (ref "X101") (pin "23") (pinfunction "23_23") (pintype "passive"))
      (node (ref "X102") (pin "1") (pinfunction "S_1") (pintype "passive"))
      (node (ref "X103") (pin "5") (pinfunction "S_5") (pintype "passive"))
    )
    (net (code "4") (name "Net-(1A-KL)") (class "Default")
      (node (ref "1") (pin "1") (pinfunction "KL_1") (pintype "passive"))
      (node (ref "D2") (pin "2") (pinfunction "-_2") (pintype "passive"))
      (node (ref "TP1") (pin "TP") (pinfunction "PP_TP") (pintype "input"))
    )
    (net (code "5") (name "Net-(1B-KL)") (class "Default")
      (node (ref "1") (pin "10") (pinfunction "KL_10") (pintype "passive"))
      (node (ref "D102") (pin "2") (pinfunction "-_2") (pintype "passive"))
      (node (ref "D103") (pin "2") (pinfunction "-_2") (pintype "passive"))
      (node (ref "JP104") (pin "1") (pinfunction "1_1") (pintype "passive"))
      (node (ref "SJ101") (pin "1") (pinfunction "1_1") (pintype "passive"))
      (node (ref "TP10") (pin "TP") (pinfunction "PP_TP") (pintype "input"))
    )
    (net (code "6") (name "Net-(1C-KL)") (class "Default")
      (node (ref "1") (pin "11") (pinfunction "KL_11") (pintype "passive"))
      (node (ref "D103") (pin "1") (pinfunction "+_1") (pintype "passive"))
      (node (ref "TP11") (pin "TP") (pinfunction "PP_TP") (pintype "input"))
      (node (ref "X101") (pin "19") (pinfunction "19_19") (pintype "passive"))
    )
    (net (code "7") (name "Net-(1E-KL)") (class "Default")
      (node (ref "1") (pin "2") (pinfunction "KL_2") (pintype "passive"))
      (node (ref "Q101") (pin "2") (pinfunction "C_2") (pintype "passive"))
      (node (ref "TP2") (pin "TP") (pinfunction "PP_TP") (pintype "input"))
    )
    (net (code "8") (name "Net-(1F-KL)") (class "Default")
      (node (ref "1") (pin "3") (pinfunction "KL_3") (pintype "passive"))
      (node (ref "IC107") (pin "11") (pinfunction "O6_11") (pintype "open_collector"))
      (node (ref "TP3") (pin "TP") (pinfunction "PP_TP") (pintype "input"))
    )
    (net (code "9") (name "Net-(1G-KL)") (class "Default")
      (node (ref "1") (pin "4") (pinfunction "KL_4") (pintype "passive"))
      (node (ref "IC107") (pin "10") (pinfunction "O7_10") (pintype "open_collector"))
      (node (ref "TP4") (pin "TP") (pinfunction "PP_TP") (pintype "input"))
    )
    (net (code "10") (name "Net-(1H-KL)") (class "Default")
      (node (ref "1") (pin "5") (pinfunction "KL_5") (pintype "passive"))
      (node (ref "IC107") (pin "12") (pinfunction "O5_12") (pintype "open_collector"))
      (node (ref "TP5") (pin "TP") (pinfunction "PP_TP") (pintype "input"))
    )
    (net (code "11") (name "Net-(1I-KL)") (class "Default")
      (node (ref "1") (pin "6") (pinfunction "KL_6") (pintype "passive"))
      (node (ref "IC107") (pin "13") (pinfunction "O4_13") (pintype "open_collector"))
      (node (ref "TP6") (pin "TP") (pinfunction "PP_TP") (pintype "input"))
    )
    (net (code "12") (name "Net-(1J-KL)") (class "Default")
      (node (ref "1") (pin "7") (pinfunction "KL_7") (pintype "passive"))
      (node (ref "IC107") (pin "14") (pinfunction "O3_14") (pintype "open_collector"))
      (node (ref "TP7") (pin "TP") (pinfunction "PP_TP") (pintype "input"))
    )
    (net (code "13") (name "Net-(1K-KL)") (class "Default")
      (node (ref "1") (pin "8") (pinfunction "KL_8") (pintype "passive"))
      (node (ref "R9") (pin "2") (pinfunction "2_2") (pintype "passive"))
      (node (ref "TP8") (pin "TP") (pinfunction "PP_TP") (pintype "input"))
    )
    (net (code "14") (name "Net-(1L-KL)") (class "Default")
      (node (ref "1") (pin "9") (pinfunction "KL_9") (pintype "passive"))
      (node (ref "D102") (pin "1") (pinfunction "+_1") (pintype "passive"))
      (node (ref "TP9") (pin "TP") (pinfunction "PP_TP") (pintype "input"))
      (node (ref "X101") (pin "17") (pinfunction "17_17") (pintype "passive"))
    )
    (net (code "15") (name "Net-(2B-KL)") (class "Default")
      (node (ref "2") (pin "10") (pinfunction "KL_10") (pintype "passive"))
      (node (ref "TP25") (pin "TP") (pinfunction "PP_TP") (pintype "input"))
      (node (ref "X101") (pin "15") (pinfunction "15_15") (pintype "passive"))
    )
    (net (code "16") (name "Net-(2C-KL)") (class "Default")
      (node (ref "2") (pin "11") (pinfunction "KL_11") (pintype "passive"))
      (node (ref "Q103") (pin "2") (pinfunction "C_2") (pintype "passive"))
      (node (ref "R119") (pin "1") (pinfunction "1_1") (pintype "passive"))
      (node (ref "TP26") (pin "TP") (pinfunction "PP_TP") (pintype "input"))
    )
    (net (code "17") (name "Net-(2D-KL)") (class "Default")
      (node (ref "2") (pin "12") (pinfunction "KL_12") (pintype "passive"))
      (node (ref "R146") (pin "1") (pinfunction "1_1") (pintype "passive"))
      (node (ref "TP13") (pin "TP") (pinfunction "PP_TP") (pintype "input"))
    )
    (net (code "18") (name "Net-(2E-KL)") (class "Default")
      (node (ref "2") (pin "2") (pinfunction "KL_2") (pintype "passive"))
      (node (ref "D109") (pin "2") (pinfunction "-_2") (pintype "passive"))
      (node (ref "LED102") (pin "K") (pinfunction "C_K") (pintype "passive"))
      (node (ref "TP16") (pin "TP") (pinfunction "PP_TP") (pintype "input"))
      (node (ref "X101") (pin "12") (pinfunction "12_12") (pintype "passive"))
    )
    (net (code "19") (name "Net-(2F-KL)") (class "Default")
      (node (ref "2") (pin "3") (pinfunction "KL_3") (pintype "passive"))
      (node (ref "D108") (pin "2") (pinfunction "-_2") (pintype "passive"))
      (node (ref "LED103") (pin "K") (pinfunction "C_K") (pintype "passive"))
      (node (ref "TP17") (pin "TP") (pinfunction "PP_TP") (pintype "input"))
      (node (ref "X101") (pin "11") (pinfunction "11_11") (pintype "passive"))
    )
    (net (code "20") (name "Net-(2G-KL)") (class "Default")
      (node (ref "2") (pin "4") (pinfunction "KL_4") (pintype "passive"))
      (node (ref "D107") (pin "2") (pinfunction "-_2") (pintype "passive"))
      (node (ref "LED104") (pin "K") (pinfunction "C_K") (pintype "passive"))
      (node (ref "TP18") (pin "TP") (pinfunction "PP_TP") (pintype "input"))
      (node (ref "X101") (pin "10") (pinfunction "10_10") (pintype "passive"))
    )
    (net (code "21") (name "Net-(2H-KL)") (class "Default")
      (node (ref "2") (pin "5") (pinfunction "KL_5") (pintype "passive"))
      (node (ref "D106") (pin "2") (pinfunction "-_2") (pintype "passive"))
      (node (ref "LED105") (pin "K") (pinfunction "C_K") (pintype "passive"))
      (node (ref "TP19") (pin "TP") (pinfunction "PP_TP") (pintype "input"))
      (node (ref "X101") (pin "9") (pinfunction "9_9") (pintype "passive"))
    )
    (net (code "22") (name "Net-(2I-KL)") (class "Default")
      (node (ref "2") (pin "6") (pinfunction "KL_6") (pintype "passive"))
      (node (ref "JP105") (pin "2") (pinfunction "2_2") (pintype "passive"))
      (node (ref "TP21") (pin "TP") (pinfunction "PP_TP") (pintype "input"))
    )
    (net (code "23") (name "Net-(2J-KL)") (class "Default")
      (node (ref "2") (pin "7") (pinfunction "KL_7") (pintype "passive"))
      (node (ref "LED101") (pin "A") (pinfunction "A_A") (pintype "passive"))
      (node (ref "TP22") (pin "TP") (pinfunction "PP_TP") (pintype "input"))
      (node (ref "X101") (pin "8") (pinfunction "8_8") (pintype "passive"))
    )
    (net (code "24") (name "Net-(2K-KL)") (class "Default")
      (node (ref "2") (pin "8") (pinfunction "KL_8") (pintype "passive"))
      (node (ref "D110") (pin "2") (pinfunction "-_2") (pintype "passive"))
      (node (ref "LED106") (pin "K") (pinfunction "C_K") (pintype "passive"))
      (node (ref "TP23") (pin "TP") (pinfunction "PP_TP") (pintype "input"))
      (node (ref "X101") (pin "14") (pinfunction "14_14") (pintype "passive"))
    )
    (net (code "25") (name "Net-(2L-KL)") (class "Default")
      (node (ref "2") (pin "9") (pinfunction "KL_9") (pintype "passive"))
      (node (ref "D107") (pin "1") (pinfunction "+_1") (pintype "passive"))
      (node (ref "D108") (pin "1") (pinfunction "+_1") (pintype "passive"))
      (node (ref "JP102") (pin "1") (pinfunction "1_1") (pintype "passive"))
      (node (ref "JP103") (pin "2") (pinfunction "2_2") (pintype "passive"))
      (node (ref "TP24") (pin "TP") (pinfunction "PP_TP") (pintype "input"))
    )
    (net (code "26") (name "Net-(C103-Pad1)") (class "Default")
      (node (ref "C103") (pin "1") (pinfunction "1_1") (pintype "passive"))
      (node (ref "R108") (pin "1") (pinfunction "1_1") (pintype "passive"))
      (node (ref "R112") (pin "1") (pinfunction "1_1") (pintype "passive"))
    )
    (net (code "27") (name "Net-(C107-Pad1)") (class "Default")
      (node (ref "C107") (pin "1") (pinfunction "1_1") (pintype "passive"))
      (node (ref "R125") (pin "1") (pinfunction "1_1") (pintype "passive"))
      (node (ref "R130") (pin "2") (pinfunction "2_2") (pintype "passive"))
    )
    (net (code "28") (name "Net-(D1--)") (class "Default")
      (node (ref "D1") (pin "2") (pinfunction "-_2") (pintype "passive"))
      (node (ref "R12") (pin "1") (pinfunction "1_1") (pintype "passive"))
      (node (ref "R13") (pin "1") (pinfunction "1_1") (pintype "passive"))
    )
    (net (code "29") (name "Net-(D2-+)") (class "Default")
      (node (ref "D2") (pin "1") (pinfunction "+_1") (pintype "passive"))
      (node (ref "X101") (pin "1") (pinfunction "1_1") (pintype "passive"))
    )
    (net (code "30") (name "Net-(D104-PadC)") (class "Default")
      (node (ref "D104") (pin "C") (pinfunction "C_C") (pintype "passive"))
      (node (ref "R105") (pin "2") (pinfunction "2_2") (pintype "passive"))
      (node (ref "X101") (pin "22") (pinfunction "22_22") (pintype "passive"))
    )
    (net (code "31") (name "Net-(D105--)") (class "Default")
      (node (ref "D105") (pin "2") (pinfunction "-_2") (pintype "passive"))
      (node (ref "Q104") (pin "2") (pinfunction "C_2") (pintype "passive"))
      (node (ref "START") (pin "TP") (pinfunction "PP_TP") (pintype "input"))
      (node (ref "X101") (pin "5") (pinfunction "5_5") (pintype "passive"))
    )
    (net (code "32") (name "Net-(D106-+)") (class "Default")
      (node (ref "D106") (pin "1") (pinfunction "+_1") (pintype "passive"))
      (node (ref "R127") (pin "1") (pinfunction "1_1") (pintype "passive"))
    )
    (net (code "33") (name "Net-(D109-+)") (class "Default")
      (node (ref "D109") (pin "1") (pinfunction "+_1") (pintype "passive"))
      (node (ref "JP102") (pin "2") (pinfunction "2_2") (pintype "passive"))
    )
    (net (code "34") (name "Net-(D110-+)") (class "Default")
      (node (ref "D110") (pin "1") (pinfunction "+_1") (pintype "passive"))
      (node (ref "JP103") (pin "1") (pinfunction "1_1") (pintype "passive"))
    )
    (net (code "35") (name "Net-(D112-+)") (class "Default")
      (node (ref "D112") (pin "1") (pinfunction "+_1") (pintype "passive"))
      (node (ref "R140") (pin "1") (pinfunction "1_1") (pintype "passive"))
    )
    (net (code "36") (name "Net-(D112--)") (class "Default")
      (node (ref "C109") (pin "2") (pinfunction "2_2") (pintype "passive"))
      (node (ref "D112") (pin "2") (pinfunction "-_2") (pintype "passive"))
      (node (ref "D4") (pin "C") (pinfunction "C_C") (pintype "passive"))
      (node (ref "IC110") (pin "2") (pinfunction "TR_2") (pintype "input"))
      (node (ref "IC110") (pin "6") (pinfunction "THR_6") (pintype "input"))
      (node (ref "R141") (pin "1") (pinfunction "1_1") (pintype "passive"))
    )
    (net (code "37") (name "Net-(IC101A-+IN)") (class "Default")
      (node (ref "C101") (pin "1") (pinfunction "1_1") (pintype "passive"))
      (node (ref "IC101") (pin "3") (pinfunction "+IN_3") (pintype "input"))
      (node (ref "R105") (pin "1") (pinfunction "1_1") (pintype "passive"))
    )
    (net (code "38") (name "Net-(IC101A--IN)") (class "Default")
      (node (ref "IC101") (pin "2") (pinfunction "-IN_2") (pintype "input"))
      (node (ref "R107") (pin "2") (pinfunction "2_2") (pintype "passive"))
    )
    (net (code "39") (name "Net-(IC101A-OUT)") (class "Default")
      (node (ref "IC101") (pin "1") (pinfunction "OUT_1") (pintype "output"))
      (node (ref "R108") (pin "2") (pinfunction "2_2") (pintype "passive"))
    )
    (net (code "40") (name "Net-(IC101B-+IN)") (class "Default")
      (node (ref "IC101") (pin "5") (pinfunction "+IN_5") (pintype "input"))
      (node (ref "Q1") (pin "3") (pinfunction "D_3") (pintype "passive"))
      (node (ref "R112") (pin "2") (pinfunction "2_2") (pintype "passive"))
      (node (ref "R117") (pin "2") (pinfunction "2_2") (pintype "passive"))
    )
    (net (code "41") (name "Net-(IC101B--IN)") (class "Default")
      (node (ref "IC101") (pin "6") (pinfunction "-IN_6") (pintype "input"))
      (node (ref "R113") (pin "1") (pinfunction "1_1") (pintype "passive"))
      (node (ref "R114") (pin "2") (pinfunction "2_2") (pintype "passive"))
    )
    (net (code "42") (name "Net-(IC101B-OUT)") (class "Default")
      (node (ref "IC101") (pin "7") (pinfunction "OUT_7") (pintype "output"))
      (node (ref "R115") (pin "2") (pinfunction "2_2") (pintype "passive"))
      (node (ref "R116") (pin "1") (pinfunction "1_1") (pintype "passive"))
      (node (ref "R117") (pin "1") (pinfunction "1_1") (pintype "passive"))
    )
    (net (code "43") (name "Net-(IC105A-A)") (class "Default")
      (node (ref "IC105") (pin "10") (pinfunction "A_10") (pintype "input"))
      (node (ref "R111") (pin "1") (pinfunction "1_1") (pintype "passive"))
      (node (ref "R3") (pin "1") (pinfunction "1_1") (pintype "passive"))
      (node (ref "R3") (pin "2") (pinfunction "2_2") (pintype "passive"))
      (node (ref "X101") (pin "4") (pinfunction "4_4") (pintype "passive"))
      (node (ref "X103") (pin "2") (pinfunction "S_2") (pintype "passive"))
    )
    (net (code "44") (name "Net-(IC105A-B)") (class "Default")
      (node (ref "IC105") (pin "13") (pinfunction "B_13") (pintype "input"))
      (node (ref "R110") (pin "1") (pinfunction "1_1") (pintype "passive"))
      (node (ref "R2") (pin "1") (pinfunction "1_1") (pintype "passive"))
      (node (ref "R2") (pin "2") (pinfunction "2_2") (pintype "passive"))
      (node (ref "X101") (pin "3") (pinfunction "3_3") (pintype "passive"))
      (node (ref "X103") (pin "3") (pinfunction "S_3") (pintype "passive"))
    )
    (net (code "45") (name "Net-(IC105A-C)") (class "Default")
      (node (ref "IC105") (pin "12") (pinfunction "C_12") (pintype "input"))
      (node (ref "R1") (pin "1") (pinfunction "1_1") (pintype "passive"))
      (node (ref "R1") (pin "2") (pinfunction "2_2") (pintype "passive"))
      (node (ref "R109") (pin "1") (pinfunction "1_1") (pintype "passive"))
      (node (ref "X101") (pin "2") (pinfunction "2_2") (pintype "passive"))
      (node (ref "X103") (pin "4") (pinfunction "S_4") (pintype "passive"))
    )
    (net (code "46") (name "Net-(IC105A-Q0)") (class "Default")
      (node (ref "IC105") (pin "3") (pinfunction "Q0_3") (pintype "output"))
      (node (ref "IC107") (pin "1") (pinfunction "I1_1") (pintype "input"))
      (node (ref "IC107") (pin "2") (pinfunction "I2_2") (pintype "input"))
      (node (ref "Q1") (pin "1") (pinfunction "G_1") (pintype "passive"))
      (node (ref "Q106") (pin "1") (pinfunction "G_1") (pintype "passive"))
    )
    (net (code "47") (name "Net-(IC105A-Q1)") (class "Default")
      (node (ref "IC105") (pin "14") (pinfunction "Q1_14") (pintype "output"))
      (node (ref "IC107") (pin "6") (pinfunction "I6_6") (pintype "input"))
    )
    (net (code "48") (name "Net-(IC105A-Q2)") (class "Default")
      (node (ref "IC105") (pin "2") (pinfunction "Q2_2") (pintype "output"))
      (node (ref "IC107") (pin "7") (pinfunction "I7_7") (pintype "input"))
    )
    (net (code "49") (name "Net-(IC105A-Q3)") (class "Default")
      (node (ref "IC105") (pin "15") (pinfunction "Q3_15") (pintype "output"))
      (node (ref "IC107") (pin "5") (pinfunction "I5_5") (pintype "input"))
    )
    (net (code "50") (name "Net-(IC105A-Q4)") (class "Default")
      (node (ref "IC105") (pin "1") (pinfunction "Q4_1") (pintype "output"))
      (node (ref "IC107") (pin "4") (pinfunction "I4_4") (pintype "input"))
    )
    (net (code "51") (name "Net-(IC105A-Q5)") (class "Default")
      (node (ref "IC105") (pin "6") (pinfunction "Q5_6") (pintype "output"))
      (node (ref "IC107") (pin "3") (pinfunction "I3_3") (pintype "input"))
    )
    (net (code "52") (name "Net-(IC107-O1)") (class "Default")
      (node (ref "IC107") (pin "16") (pinfunction "O1_16") (pintype "open_collector"))
      (node (ref "Q106") (pin "3") (pinfunction "D_3") (pintype "passive"))
      (node (ref "R9") (pin "1") (pinfunction "1_1") (pintype "passive"))
    )
    (net (code "53") (name "Net-(IC107-O2)") (class "Default")
      (node (ref "IC107") (pin "15") (pinfunction "O2_15") (pintype "open_collector"))
      (node (ref "R128") (pin "1") (pinfunction "1_1") (pintype "passive"))
    )
    (net (code "54") (name "Net-(IC108A-+IN)") (class "Default")
      (node (ref "IC108") (pin "11") (pinfunction "+IN_11") (pintype "input"))
      (node (ref "IC108") (pin "5") (pinfunction "+IN_5") (pintype "input"))
      (node (ref "R131") (pin "1") (pinfunction "1_1") (pintype "passive"))
      (node (ref "R132") (pin "2") (pinfunction "2_2") (pintype "passive"))
      (node (ref "R133") (pin "2") (pinfunction "2_2") (pintype "passive"))
    )
    (net (code "55") (name "Net-(IC108A--IN)") (class "Default")
      (node (ref "C108") (pin "1") (pinfunction "1_1") (pintype "passive"))
      (node (ref "IC108") (pin "10") (pinfunction "-IN_10") (pintype "input"))
      (node (ref "IC108") (pin "4") (pinfunction "-IN_4") (pintype "input"))
      (node (ref "R130") (pin "1") (pinfunction "1_1") (pintype "passive"))
    )
    (net (code "56") (name "Net-(IC108A-OUT)") (class "Default")
      (node (ref "IC108") (pin "2") (pinfunction "OUT_2") (pintype "open_collector"))
      (node (ref "R133") (pin "1") (pinfunction "1_1") (pintype "passive"))
    )
    (net (code "57") (name "Net-(IC108B-+IN)") (class "Default")
      (node (ref "IC108") (pin "7") (pinfunction "+IN_7") (pintype "input"))
      (node (ref "R121") (pin "1") (pinfunction "1_1") (pintype "passive"))
      (node (ref "R122") (pin "1") (pinfunction "1_1") (pintype "passive"))
    )
    (net (code "58") (name "Net-(IC108B--IN)") (class "Default")
      (node (ref "IC108") (pin "6") (pinfunction "-IN_6") (pintype "input"))
      (node (ref "IC108") (pin "8") (pinfunction "-IN_8") (pintype "input"))
      (node (ref "R120") (pin "1") (pinfunction "1_1") (pintype "passive"))
    )
    (net (code "59") (name "Net-(IC108B-OUT)") (class "Default")
      (node (ref "IC108") (pin "1") (pinfunction "OUT_1") (pintype "open_collector"))
      (node (ref "R124") (pin "2") (pinfunction "2_2") (pintype "passive"))
      (node (ref "R125") (pin "2") (pinfunction "2_2") (pintype "passive"))
    )
    (net (code "60") (name "Net-(IC108C-+IN)") (class "Default")
      (node (ref "C105") (pin "1") (pinfunction "1_1") (pintype "passive"))
      (node (ref "IC108") (pin "9") (pinfunction "+IN_9") (pintype "input"))
      (node (ref "R122") (pin "2") (pinfunction "2_2") (pintype "passive"))
      (node (ref "R123") (pin "2") (pinfunction "2_2") (pintype "passive"))
    )
    (net (code "61") (name "Net-(IC108C-OUT)") (class "Default")
      (node (ref "C106") (pin "2") (pinfunction "2_2") (pintype "passive"))
      (node (ref "IC108") (pin "14") (pinfunction "OUT_14") (pintype "open_collector"))
      (node (ref "R126") (pin "2") (pinfunction "2_2") (pintype "passive"))
    )
    (net (code "62") (name "Net-(IC108D-OUT)") (class "Default")
      (node (ref "IC108") (pin "13") (pinfunction "OUT_13") (pintype "open_collector"))
      (node (ref "JP105") (pin "1") (pinfunction "1_1") (pintype "passive"))
      (node (ref "Q107") (pin "1") (pinfunction "G_1") (pintype "passive"))
      (node (ref "R135") (pin "2") (pinfunction "2_2") (pintype "passive"))
    )
    (net (code "63") (name "Net-(IC109-ADJ)") (class "Default")
      (node (ref "IC109") (pin "1") (pinfunction "ADJ_1") (pintype "input"))
      (node (ref "R120") (pin "2") (pinfunction "2_2") (pintype "passive"))
      (node (ref "R134") (pin "1") (pinfunction "1_1") (pintype "passive"))
      (node (ref "X101") (pin "7") (pinfunction "7_7") (pintype "passive"))
    )
    (net (code "64") (name "Net-(IC109-VI)") (class "Default")
      (node (ref "IC109") (pin "3") (pinfunction "VI_3") (pintype "input"))
      (node (ref "Q105") (pin "2") (pinfunction "C_2") (pintype "passive"))
    )
    (net (code "65") (name "Net-(IC109-VO)") (class "Default")
      (node (ref "IC109") (pin "2") (pinfunction "VO_2") (pintype "passive"))
      (node (ref "R134") (pin "2") (pinfunction "2_2") (pintype "passive"))
    )
    (net (code "66") (name "Net-(IC110-CV)") (class "Default")
      (node (ref "IC110") (pin "5") (pinfunction "CV_5") (pintype "input"))
      (node (ref "R144") (pin "2") (pinfunction "2_2") (pintype "passive"))
    )
    (net (code "67") (name "Net-(IC110-Q)") (class "Default")
      (node (ref "IC110") (pin "3") (pinfunction "Q_3") (pintype "output"))
      (node (ref "IC111") (pin "12") (pinfunction "A_12") (pintype "input"))
      (node (ref "IC111") (pin "4") (pinfunction "A_4") (pintype "input"))
      (node (ref "R144") (pin "1") (pinfunction "1_1") (pintype "passive"))
    )
    (net (code "68") (name "Net-(IC111A-T2)") (class "Default")
      (node (ref "C15") (pin "2") (pinfunction "2_2") (pintype "passive"))
      (node (ref "IC111") (pin "2") (pinfunction "T2_2") (pintype "input"))
      (node (ref "R10") (pin "1") (pinfunction "1_1") (pintype "passive"))
    )
    (net (code "69") (name "Net-(IC111A-~{Q})") (class "Default")
      (node (ref "IC111") (pin "7") (pinfunction "~{Q}_7") (pintype "output"))
      (node (ref "Q3") (pin "1") (pinfunction "G_1") (pintype "passive"))
    )
    (net (code "70") (name "Net-(IC111B-B)") (class "Default")
      (node (ref "IC111") (pin "11") (pinfunction "B_11") (pintype "input"))
      (node (ref "IC111") (pin "9") (pinfunction "~{Q}_9") (pintype "output"))
      (node (ref "R146") (pin "2") (pinfunction "2_2") (pintype "passive"))
    )
    (net (code "71") (name "Net-(IC111B-T2)") (class "Default")
      (node (ref "C110") (pin "1") (pinfunction "1_1") (pintype "passive"))
      (node (ref "IC111") (pin "14") (pinfunction "T2_14") (pintype "input"))
      (node (ref "R145") (pin "1") (pinfunction "1_1") (pintype "passive"))
    )
    (net (code "72") (name "Net-(JP101-Pad1)") (class "Default")
      (node (ref "JP101") (pin "1") (pinfunction "1_1") (pintype "passive"))
      (node (ref "R119") (pin "2") (pinfunction "2_2") (pintype "passive"))
    )
    (net (code "73") (name "Net-(JP104-Pad2)") (class "Default")
      (node (ref "JP104") (pin "2") (pinfunction "2_2") (pintype "passive"))
      (node (ref "R136") (pin "2") (pinfunction "2_2") (pintype "passive"))
      (node (ref "R137") (pin "2") (pinfunction "2_2") (pintype "passive"))
      (node (ref "SJ101") (pin "2") (pinfunction "2_2") (pintype "passive"))
    )
    (net (code "74") (name "Net-(JP105-Pad3)") (class "Default")
      (node (ref "JP105") (pin "3") (pinfunction "3_3") (pintype "passive"))
      (node (ref "R138") (pin "1") (pinfunction "1_1") (pintype "passive"))
    )
    (net (code "75") (name "Net-(LED101-C)") (class "Default")
      (node (ref "LED101") (pin "K") (pinfunction "C_K") (pintype "passive"))
      (node (ref "R143") (pin "1") (pinfunction "1_1") (pintype "passive"))
    )
    (net (code "76") (name "Net-(LED102-PadA)") (class "Default")
      (node (ref "LED102") (pin "A") (pinfunction "A_A") (pintype "passive"))
      (node (ref "LED103") (pin "A") (pinfunction "A_A") (pintype "passive"))
      (node (ref "LED104") (pin "A") (pinfunction "A_A") (pintype "passive"))
      (node (ref "LED105") (pin "A") (pinfunction "A_A") (pintype "passive"))
      (node (ref "LED106") (pin "A") (pinfunction "A_A") (pintype "passive"))
      (node (ref "R142") (pin "1") (pinfunction "1_1") (pintype "passive"))
    )
    (net (code "77") (name "Net-(Q2-B)") (class "Default")
      (node (ref "Q2") (pin "1") (pinfunction "B_1") (pintype "passive"))
      (node (ref "R8") (pin "1") (pinfunction "1_1") (pintype "passive"))
    )
    (net (code "78") (name "Net-(Q2-C)") (class "Default")
      (node (ref "Q2") (pin "2") (pinfunction "C_2") (pintype "passive"))
      (node (ref "R129") (pin "2") (pinfunction "2_2") (pintype "passive"))
      (node (ref "SJMP") (pin "2") (pinfunction "2_2") (pintype "passive"))
    )
    (net (code "79") (name "Net-(Q3-D)") (class "Default")
      (node (ref "Q3") (pin "3") (pinfunction "D_3") (pintype "passive"))
      (node (ref "R8") (pin "2") (pinfunction "2_2") (pintype "passive"))
    )
    (net (code "80") (name "Net-(Q101-B)") (class "Default")
      (node (ref "Q101") (pin "1") (pinfunction "B_1") (pintype "passive"))
      (node (ref "Q102") (pin "1") (pinfunction "B_1") (pintype "passive"))
      (node (ref "Q102") (pin "2") (pinfunction "C_2") (pintype "passive"))
      (node (ref "R101") (pin "1") (pinfunction "1_1") (pintype "passive"))
      (node (ref "R103") (pin "1") (pinfunction "1_1") (pintype "passive"))
      (node (ref "R104") (pin "1") (pinfunction "1_1") (pintype "passive"))
      (node (ref "X102") (pin "2") (pinfunction "S_2") (pintype "passive"))
    )
    (net (code "81") (name "Net-(Q101-E)") (class "Default")
      (node (ref "Q101") (pin "3") (pinfunction "E_3") (pintype "passive"))
      (node (ref "R102") (pin "2") (pinfunction "2_2") (pintype "passive"))
    )
    (net (code "82") (name "Net-(Q102-E)") (class "Default")
      (node (ref "Q102") (pin "3") (pinfunction "E_3") (pintype "passive"))
      (node (ref "R106") (pin "2") (pinfunction "2_2") (pintype "passive"))
    )
    (net (code "83") (name "Net-(Q103-B)") (class "Default")
      (node (ref "Q103") (pin "1") (pinfunction "B_1") (pintype "passive"))
      (node (ref "R116") (pin "2") (pinfunction "2_2") (pintype "passive"))
      (node (ref "R6") (pin "1") (pinfunction "1_1") (pintype "passive"))
    )
    (net (code "84") (name "Net-(Q103-E)") (class "Default")
      (node (ref "Q103") (pin "3") (pinfunction "E_3") (pintype "passive"))
      (node (ref "R5") (pin "1") (pinfunction "1_1") (pintype "passive"))
    )
    (net (code "85") (name "Net-(Q104-B)") (class "Default")
      (node (ref "Q104") (pin "1") (pinfunction "B_1") (pintype "passive"))
      (node (ref "R128") (pin "2") (pinfunction "2_2") (pintype "passive"))
    )
    (net (code "86") (name "Net-(Q105-B)") (class "Default")
      (node (ref "Q105") (pin "1") (pinfunction "B_1") (pintype "passive"))
      (node (ref "R126") (pin "1") (pinfunction "1_1") (pintype "passive"))
    )
    (net (code "87") (name "Net-(Q106-S)") (class "Default")
      (node (ref "Q106") (pin "2") (pinfunction "S_2") (pintype "passive"))
      (node (ref "R4") (pin "2") (pinfunction "2_2") (pintype "passive"))
    )
    (net (code "88") (name "Net-(Q107-D)") (class "Default")
      (node (ref "Q107") (pin "3") (pinfunction "D_3") (pintype "passive"))
      (node (ref "R138") (pin "2") (pinfunction "2_2") (pintype "passive"))
    )
    (net (code "89") (name "Net-(R115-Pad1)") (class "Default")
      (node (ref "R115") (pin "1") (pinfunction "1_1") (pintype "passive"))
      (node (ref "X101") (pin "21") (pinfunction "21_21") (pintype "passive"))
    )
    (net (code "90") (name "Net-(R127-Pad2)") (class "Default")
      (node (ref "R127") (pin "2") (pinfunction "2_2") (pintype "passive"))
      (node (ref "R129") (pin "1") (pinfunction "1_1") (pintype "passive"))
    )
    (net (code "91") (name "Net-(R140-Pad2)") (class "Default")
      (node (ref "R140") (pin "2") (pinfunction "2_2") (pintype "passive"))
      (node (ref "X101") (pin "16") (pinfunction "16_16") (pintype "passive"))
    )
    (net (code "92") (name "V+") (class "Default")
      (node (ref "D1") (pin "1") (pinfunction "+_1") (pintype "passive"))
      (node (ref "Q104") (pin "3") (pinfunction "E_3") (pintype "passive"))
      (node (ref "Q105") (pin "3") (pinfunction "E_3") (pintype "passive"))
      (node (ref "Q2") (pin "3") (pinfunction "E_3") (pintype "passive"))
      (node (ref "SJMP") (pin "1") (pinfunction "1_1") (pintype "passive"))
      (node (ref "X101") (pin "6") (pinfunction "6_6") (pintype "passive"))
    )
    (net (code "93") (name "VCC") (class "Default")
      (node (ref "6V") (pin "TP") (pinfunction "PP_TP") (pintype "input"))
      (node (ref "C104") (pin "1") (pinfunction "1_1") (pintype "passive"))
      (node (ref "IC101") (pin "8") (pinfunction "V+_8") (pintype "power_in"))
      (node (ref "IC102") (pin "1") (pinfunction "OUT_1") (pintype "passive"))
      (node (ref "IC108") (pin "3") (pinfunction "V+_3") (pintype "power_in"))
      (node (ref "R113") (pin "2") (pinfunction "2_2") (pintype "passive"))
      (node (ref "R121") (pin "2") (pinfunction "2_2") (pintype "passive"))
      (node (ref "R124") (pin "1") (pinfunction "1_1") (pintype "passive"))
      (node (ref "R131") (pin "2") (pinfunction "2_2") (pintype "passive"))
      (node (ref "R142") (pin "2") (pinfunction "2_2") (pintype "passive"))
    )
    (net (code "94") (name "unconnected-(IC105A-Q6-Pad7)") (class "Default")
      (node (ref "IC105") (pin "7") (pinfunction "Q6_7") (pintype "output"))
    )
    (net (code "95") (name "unconnected-(IC105A-Q7-Pad4)") (class "Default")
      (node (ref "IC105") (pin "4") (pinfunction "Q7_4") (pintype "output"))
    )
    (net (code "96") (name "unconnected-(IC105A-Q8-Pad9)") (class "Default")
      (node (ref "IC105") (pin "9") (pinfunction "Q8_9") (pintype "output"))
    )
    (net (code "97") (name "unconnected-(IC105A-Q9-Pad5)") (class "Default")
      (node (ref "IC105") (pin "5") (pinfunction "Q9_5") (pintype "output"))
    )
    (net (code "98") (name "unconnected-(IC110-DIS-Pad7)") (class "Default")
      (node (ref "IC110") (pin "7") (pinfunction "DIS_7") (pintype "input"))
    )
    (net (code "99") (name "unconnected-(IC111A-Q-Pad6)") (class "Default")
      (node (ref "IC111") (pin "6") (pinfunction "Q_6") (pintype "output"))
    )
    (net (code "100") (name "unconnected-(IC111B-Q-Pad10)") (class "Default")
      (node (ref "IC111") (pin "10") (pinfunction "Q_10") (pintype "output"))
    )
    (net (code "101") (name "unconnected-(X101-Pad20)") (class "Default")
      (node (ref "X101") (pin "20") (pinfunction "20_20") (pintype "passive"))
    )
    (net (code "102") (name "unconnected-(X101-Pad24)") (class "Default")
      (node (ref "X101") (pin "24") (pinfunction "24_24") (pintype "passive"))
    )
  )
)
